# Voltage_Sensing.net
KiCad netlist of a schematic drawn in Altium Designer
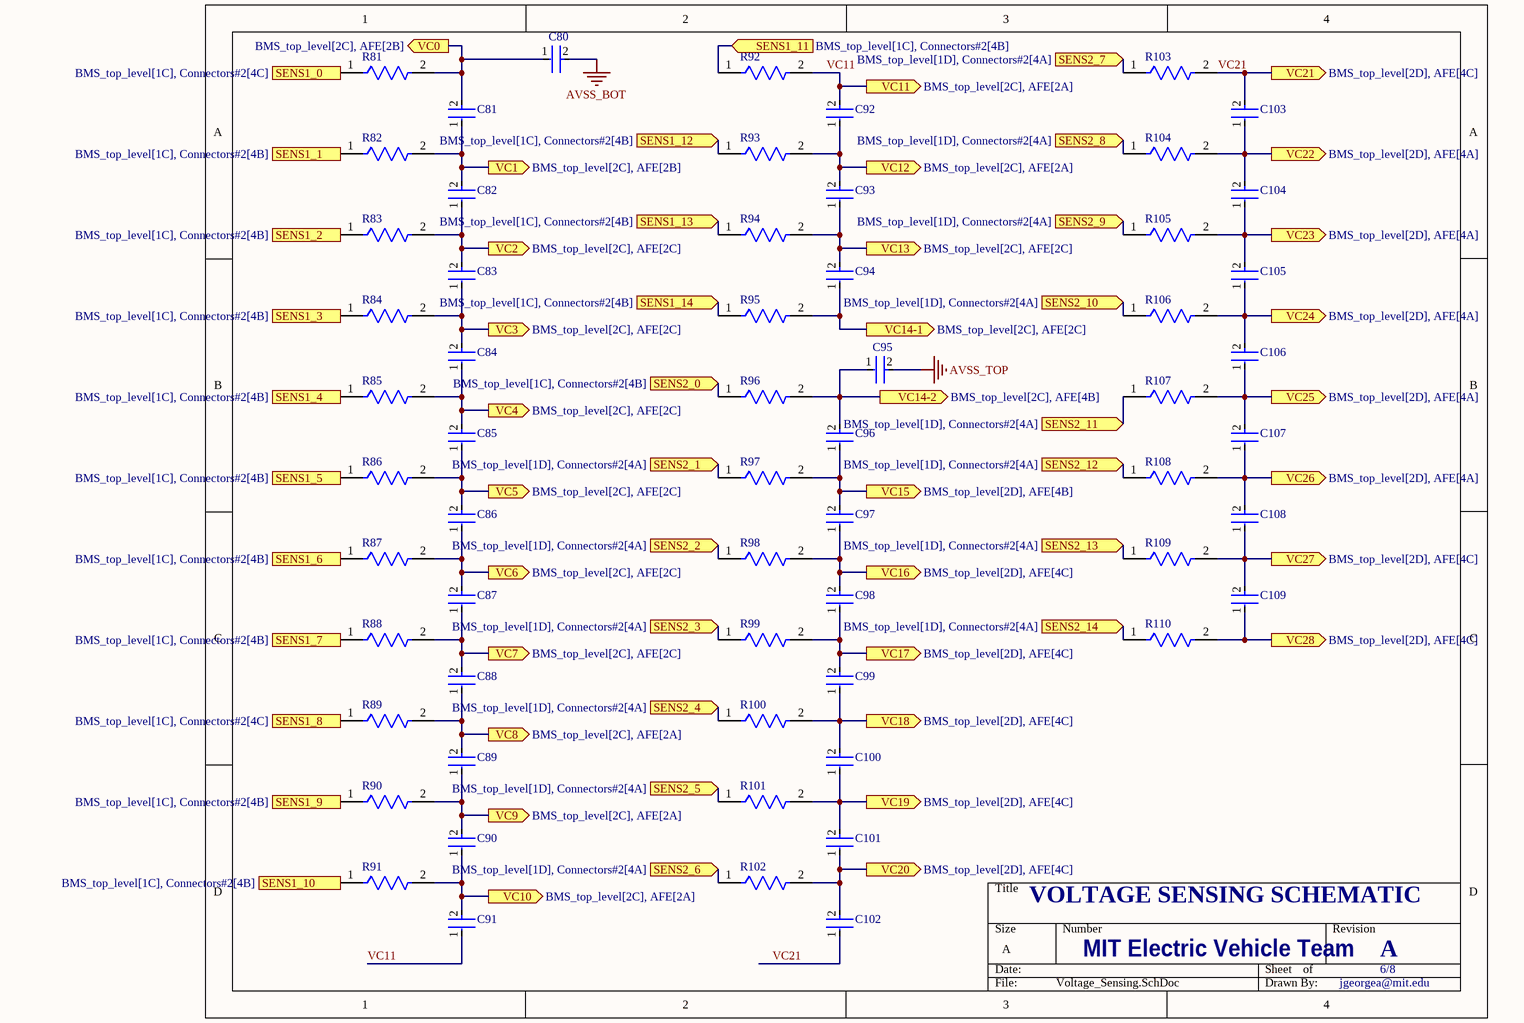
[diagram p0: Voltage_Sensing.SchDoc]

(export (version "E")
  (design (tool "Eeschema 10.0.6"))
  (components
    (comp (ref "C80")
      (value "C1608X7R1C474K080AC")
      (footprint "FP-C1608-080-0_1-IPC_C")
      (description "Multilayer Ceramic Capacitors 470nF ±10% 16V X7R SMD 0603")
      (fields (field (name "VOLTAGE") "16V") (field (name "TOLERANCE") "10%"))
      (libsource (lib "Altium Content Vault") (part "236180d848d6139a670b325ea6854c9"))
    )
    (comp (ref "C81")
      (value "C1608X7R1C474K080AC")
      (footprint "FP-C1608-080-0_1-IPC_C")
      (description "Multilayer Ceramic Capacitors 470nF ±10% 16V X7R SMD 0603")
      (fields (field (name "VOLTAGE") "16V") (field (name "TOLERANCE") "10%"))
      (libsource (lib "Altium Content Vault") (part "236180d848d6139a670b325ea6854c9"))
    )
    (comp (ref "C82")
      (value "C1608X7R1C474K080AC")
      (footprint "FP-C1608-080-0_1-IPC_C")
      (description "Multilayer Ceramic Capacitors 470nF ±10% 16V X7R SMD 0603")
      (fields (field (name "VOLTAGE") "16V") (field (name "TOLERANCE") "10%"))
      (libsource (lib "Altium Content Vault") (part "236180d848d6139a670b325ea6854c9"))
    )
    (comp (ref "C83")
      (value "C1608X7R1C474K080AC")
      (footprint "FP-C1608-080-0_1-IPC_C")
      (description "Multilayer Ceramic Capacitors 470nF ±10% 16V X7R SMD 0603")
      (fields (field (name "VOLTAGE") "16V") (field (name "TOLERANCE") "10%"))
      (libsource (lib "Altium Content Vault") (part "236180d848d6139a670b325ea6854c9"))
    )
    (comp (ref "C84")
      (value "C1608X7R1C474K080AC")
      (footprint "FP-C1608-080-0_1-IPC_C")
      (description "Multilayer Ceramic Capacitors 470nF ±10% 16V X7R SMD 0603")
      (fields (field (name "VOLTAGE") "16V") (field (name "TOLERANCE") "10%"))
      (libsource (lib "Altium Content Vault") (part "236180d848d6139a670b325ea6854c9"))
    )
    (comp (ref "C85")
      (value "C1608X7R1C474K080AC")
      (footprint "FP-C1608-080-0_1-IPC_C")
      (description "Multilayer Ceramic Capacitors 470nF ±10% 16V X7R SMD 0603")
      (fields (field (name "VOLTAGE") "16V") (field (name "TOLERANCE") "10%"))
      (libsource (lib "Altium Content Vault") (part "236180d848d6139a670b325ea6854c9"))
    )
    (comp (ref "C86")
      (value "C1608X7R1C474K080AC")
      (footprint "FP-C1608-080-0_1-IPC_C")
      (description "Multilayer Ceramic Capacitors 470nF ±10% 16V X7R SMD 0603")
      (fields (field (name "VOLTAGE") "16V") (field (name "TOLERANCE") "10%"))
      (libsource (lib "Altium Content Vault") (part "236180d848d6139a670b325ea6854c9"))
    )
    (comp (ref "C87")
      (value "C1608X7R1C474K080AC")
      (footprint "FP-C1608-080-0_1-IPC_C")
      (description "Multilayer Ceramic Capacitors 470nF ±10% 16V X7R SMD 0603")
      (fields (field (name "VOLTAGE") "16V") (field (name "TOLERANCE") "10%"))
      (libsource (lib "Altium Content Vault") (part "236180d848d6139a670b325ea6854c9"))
    )
    (comp (ref "C88")
      (value "C1608X7R1C474K080AC")
      (footprint "FP-C1608-080-0_1-IPC_C")
      (description "Multilayer Ceramic Capacitors 470nF ±10% 16V X7R SMD 0603")
      (fields (field (name "VOLTAGE") "16V") (field (name "TOLERANCE") "10%"))
      (libsource (lib "Altium Content Vault") (part "236180d848d6139a670b325ea6854c9"))
    )
    (comp (ref "C89")
      (value "C1608X7R1C474K080AC")
      (footprint "FP-C1608-080-0_1-IPC_C")
      (description "Multilayer Ceramic Capacitors 470nF ±10% 16V X7R SMD 0603")
      (fields (field (name "VOLTAGE") "16V") (field (name "TOLERANCE") "10%"))
      (libsource (lib "Altium Content Vault") (part "236180d848d6139a670b325ea6854c9"))
    )
    (comp (ref "C90")
      (value "C1608X7R1C474K080AC")
      (footprint "FP-C1608-080-0_1-IPC_C")
      (description "Multilayer Ceramic Capacitors 470nF ±10% 16V X7R SMD 0603")
      (fields (field (name "VOLTAGE") "16V") (field (name "TOLERANCE") "10%"))
      (libsource (lib "Altium Content Vault") (part "236180d848d6139a670b325ea6854c9"))
    )
    (comp (ref "C91")
      (value "C1608X7R1C474K080AC")
      (footprint "FP-C1608-080-0_1-IPC_C")
      (description "Multilayer Ceramic Capacitors 470nF ±10% 16V X7R SMD 0603")
      (fields (field (name "VOLTAGE") "16V") (field (name "TOLERANCE") "10%"))
      (libsource (lib "Altium Content Vault") (part "236180d848d6139a670b325ea6854c9"))
    )
    (comp (ref "C92")
      (value "C1608X7R1C474K080AC")
      (footprint "FP-C1608-080-0_1-IPC_C")
      (description "Multilayer Ceramic Capacitors 470nF ±10% 16V X7R SMD 0603")
      (fields (field (name "VOLTAGE") "16V") (field (name "TOLERANCE") "10%"))
      (libsource (lib "Altium Content Vault") (part "236180d848d6139a670b325ea6854c9"))
    )
    (comp (ref "C93")
      (value "C1608X7R1C474K080AC")
      (footprint "FP-C1608-080-0_1-IPC_C")
      (description "Multilayer Ceramic Capacitors 470nF ±10% 16V X7R SMD 0603")
      (fields (field (name "VOLTAGE") "16V") (field (name "TOLERANCE") "10%"))
      (libsource (lib "Altium Content Vault") (part "236180d848d6139a670b325ea6854c9"))
    )
    (comp (ref "C94")
      (value "C1608X7R1C474K080AC")
      (footprint "FP-C1608-080-0_1-IPC_C")
      (description "Multilayer Ceramic Capacitors 470nF ±10% 16V X7R SMD 0603")
      (fields (field (name "VOLTAGE") "16V") (field (name "TOLERANCE") "10%"))
      (libsource (lib "Altium Content Vault") (part "236180d848d6139a670b325ea6854c9"))
    )
    (comp (ref "C95")
      (value "C1608X7R1C474K080AC")
      (footprint "FP-C1608-080-0_1-IPC_C")
      (description "Multilayer Ceramic Capacitors 470nF ±10% 16V X7R SMD 0603")
      (fields (field (name "VOLTAGE") "16V") (field (name "TOLERANCE") "10%"))
      (libsource (lib "Altium Content Vault") (part "236180d848d6139a670b325ea6854c9"))
    )
    (comp (ref "C96")
      (value "C1608X7R1C474K080AC")
      (footprint "FP-C1608-080-0_1-IPC_C")
      (description "Multilayer Ceramic Capacitors 470nF ±10% 16V X7R SMD 0603")
      (fields (field (name "VOLTAGE") "16V") (field (name "TOLERANCE") "10%"))
      (libsource (lib "Altium Content Vault") (part "236180d848d6139a670b325ea6854c9"))
    )
    (comp (ref "C97")
      (value "C1608X7R1C474K080AC")
      (footprint "FP-C1608-080-0_1-IPC_C")
      (description "Multilayer Ceramic Capacitors 470nF ±10% 16V X7R SMD 0603")
      (fields (field (name "VOLTAGE") "16V") (field (name "TOLERANCE") "10%"))
      (libsource (lib "Altium Content Vault") (part "236180d848d6139a670b325ea6854c9"))
    )
    (comp (ref "C98")
      (value "C1608X7R1C474K080AC")
      (footprint "FP-C1608-080-0_1-IPC_C")
      (description "Multilayer Ceramic Capacitors 470nF ±10% 16V X7R SMD 0603")
      (fields (field (name "VOLTAGE") "16V") (field (name "TOLERANCE") "10%"))
      (libsource (lib "Altium Content Vault") (part "236180d848d6139a670b325ea6854c9"))
    )
    (comp (ref "C99")
      (value "C1608X7R1C474K080AC")
      (footprint "FP-C1608-080-0_1-IPC_C")
      (description "Multilayer Ceramic Capacitors 470nF ±10% 16V X7R SMD 0603")
      (fields (field (name "VOLTAGE") "16V") (field (name "TOLERANCE") "10%"))
      (libsource (lib "Altium Content Vault") (part "236180d848d6139a670b325ea6854c9"))
    )
    (comp (ref "C100")
      (value "C1608X7R1C474K080AC")
      (footprint "FP-C1608-080-0_1-IPC_C")
      (description "Multilayer Ceramic Capacitors 470nF ±10% 16V X7R SMD 0603")
      (fields (field (name "VOLTAGE") "16V") (field (name "TOLERANCE") "10%"))
      (libsource (lib "Altium Content Vault") (part "236180d848d6139a670b325ea6854c9"))
    )
    (comp (ref "C101")
      (value "C1608X7R1C474K080AC")
      (footprint "FP-C1608-080-0_1-IPC_C")
      (description "Multilayer Ceramic Capacitors 470nF ±10% 16V X7R SMD 0603")
      (fields (field (name "VOLTAGE") "16V") (field (name "TOLERANCE") "10%"))
      (libsource (lib "Altium Content Vault") (part "236180d848d6139a670b325ea6854c9"))
    )
    (comp (ref "C102")
      (value "C1608X7R1C474K080AC")
      (footprint "FP-C1608-080-0_1-IPC_C")
      (description "Multilayer Ceramic Capacitors 470nF ±10% 16V X7R SMD 0603")
      (fields (field (name "VOLTAGE") "16V") (field (name "TOLERANCE") "10%"))
      (libsource (lib "Altium Content Vault") (part "236180d848d6139a670b325ea6854c9"))
    )
    (comp (ref "C103")
      (value "C1608X7R1C474K080AC")
      (footprint "FP-C1608-080-0_1-IPC_C")
      (description "Multilayer Ceramic Capacitors 470nF ±10% 16V X7R SMD 0603")
      (fields (field (name "VOLTAGE") "16V") (field (name "TOLERANCE") "10%"))
      (libsource (lib "Altium Content Vault") (part "236180d848d6139a670b325ea6854c9"))
    )
    (comp (ref "C104")
      (value "C1608X7R1C474K080AC")
      (footprint "FP-C1608-080-0_1-IPC_C")
      (description "Multilayer Ceramic Capacitors 470nF ±10% 16V X7R SMD 0603")
      (fields (field (name "VOLTAGE") "16V") (field (name "TOLERANCE") "10%"))
      (libsource (lib "Altium Content Vault") (part "236180d848d6139a670b325ea6854c9"))
    )
    (comp (ref "C105")
      (value "C1608X7R1C474K080AC")
      (footprint "FP-C1608-080-0_1-IPC_C")
      (description "Multilayer Ceramic Capacitors 470nF ±10% 16V X7R SMD 0603")
      (fields (field (name "VOLTAGE") "16V") (field (name "TOLERANCE") "10%"))
      (libsource (lib "Altium Content Vault") (part "236180d848d6139a670b325ea6854c9"))
    )
    (comp (ref "C106")
      (value "C1608X7R1C474K080AC")
      (footprint "FP-C1608-080-0_1-IPC_C")
      (description "Multilayer Ceramic Capacitors 470nF ±10% 16V X7R SMD 0603")
      (fields (field (name "VOLTAGE") "16V") (field (name "TOLERANCE") "10%"))
      (libsource (lib "Altium Content Vault") (part "236180d848d6139a670b325ea6854c9"))
    )
    (comp (ref "C107")
      (value "C1608X7R1C474K080AC")
      (footprint "FP-C1608-080-0_1-IPC_C")
      (description "Multilayer Ceramic Capacitors 470nF ±10% 16V X7R SMD 0603")
      (fields (field (name "VOLTAGE") "16V") (field (name "TOLERANCE") "10%"))
      (libsource (lib "Altium Content Vault") (part "236180d848d6139a670b325ea6854c9"))
    )
    (comp (ref "C108")
      (value "C1608X7R1C474K080AC")
      (footprint "FP-C1608-080-0_1-IPC_C")
      (description "Multilayer Ceramic Capacitors 470nF ±10% 16V X7R SMD 0603")
      (fields (field (name "VOLTAGE") "16V") (field (name "TOLERANCE") "10%"))
      (libsource (lib "Altium Content Vault") (part "236180d848d6139a670b325ea6854c9"))
    )
    (comp (ref "C109")
      (value "C1608X7R1C474K080AC")
      (footprint "FP-C1608-080-0_1-IPC_C")
      (description "Multilayer Ceramic Capacitors 470nF ±10% 16V X7R SMD 0603")
      (fields (field (name "VOLTAGE") "16V") (field (name "TOLERANCE") "10%"))
      (libsource (lib "Altium Content Vault") (part "236180d848d6139a670b325ea6854c9"))
    )
    (comp (ref "R81")
      (value "CRCW0805100RJNEAHP")
      (footprint "FP-CRCW0805-HPe3-IPC_C")
      (description "RES Thick Film, 100Ω, 5%, 0.5W, 200ppm/°C, 0805")
      (fields (field (name "TOLERANCE") "5%"))
      (libsource (lib "Altium Content Vault") (part "1029c3af85768c4190bb7ad29bc67b5"))
    )
    (comp (ref "R82")
      (value "CRCW0805100RJNEAHP")
      (footprint "FP-CRCW0805-HPe3-IPC_C")
      (description "RES Thick Film, 100Ω, 5%, 0.5W, 200ppm/°C, 0805")
      (fields (field (name "TOLERANCE") "5%"))
      (libsource (lib "Altium Content Vault") (part "1029c3af85768c4190bb7ad29bc67b5"))
    )
    (comp (ref "R83")
      (value "CRCW0805100RJNEAHP")
      (footprint "FP-CRCW0805-HPe3-IPC_C")
      (description "RES Thick Film, 100Ω, 5%, 0.5W, 200ppm/°C, 0805")
      (fields (field (name "TOLERANCE") "5%"))
      (libsource (lib "Altium Content Vault") (part "1029c3af85768c4190bb7ad29bc67b5"))
    )
    (comp (ref "R84")
      (value "CRCW0805100RJNEAHP")
      (footprint "FP-CRCW0805-HPe3-IPC_C")
      (description "RES Thick Film, 100Ω, 5%, 0.5W, 200ppm/°C, 0805")
      (fields (field (name "TOLERANCE") "5%"))
      (libsource (lib "Altium Content Vault") (part "1029c3af85768c4190bb7ad29bc67b5"))
    )
    (comp (ref "R85")
      (value "CRCW0805100RJNEAHP")
      (footprint "FP-CRCW0805-HPe3-IPC_C")
      (description "RES Thick Film, 100Ω, 5%, 0.5W, 200ppm/°C, 0805")
      (fields (field (name "TOLERANCE") "5%"))
      (libsource (lib "Altium Content Vault") (part "1029c3af85768c4190bb7ad29bc67b5"))
    )
    (comp (ref "R86")
      (value "CRCW0805100RJNEAHP")
      (footprint "FP-CRCW0805-HPe3-IPC_C")
      (description "RES Thick Film, 100Ω, 5%, 0.5W, 200ppm/°C, 0805")
      (fields (field (name "TOLERANCE") "5%"))
      (libsource (lib "Altium Content Vault") (part "1029c3af85768c4190bb7ad29bc67b5"))
    )
    (comp (ref "R87")
      (value "CRCW0805100RJNEAHP")
      (footprint "FP-CRCW0805-HPe3-IPC_C")
      (description "RES Thick Film, 100Ω, 5%, 0.5W, 200ppm/°C, 0805")
      (fields (field (name "TOLERANCE") "5%"))
      (libsource (lib "Altium Content Vault") (part "1029c3af85768c4190bb7ad29bc67b5"))
    )
    (comp (ref "R88")
      (value "CRCW0805100RJNEAHP")
      (footprint "FP-CRCW0805-HPe3-IPC_C")
      (description "RES Thick Film, 100Ω, 5%, 0.5W, 200ppm/°C, 0805")
      (fields (field (name "TOLERANCE") "5%"))
      (libsource (lib "Altium Content Vault") (part "1029c3af85768c4190bb7ad29bc67b5"))
    )
    (comp (ref "R89")
      (value "CRCW0805100RJNEAHP")
      (footprint "FP-CRCW0805-HPe3-IPC_C")
      (description "RES Thick Film, 100Ω, 5%, 0.5W, 200ppm/°C, 0805")
      (fields (field (name "TOLERANCE") "5%"))
      (libsource (lib "Altium Content Vault") (part "1029c3af85768c4190bb7ad29bc67b5"))
    )
    (comp (ref "R90")
      (value "CRCW0805100RJNEAHP")
      (footprint "FP-CRCW0805-HPe3-IPC_C")
      (description "RES Thick Film, 100Ω, 5%, 0.5W, 200ppm/°C, 0805")
      (fields (field (name "TOLERANCE") "5%"))
      (libsource (lib "Altium Content Vault") (part "1029c3af85768c4190bb7ad29bc67b5"))
    )
    (comp (ref "R91")
      (value "CRCW0805100RJNEAHP")
      (footprint "FP-CRCW0805-HPe3-IPC_C")
      (description "RES Thick Film, 100Ω, 5%, 0.5W, 200ppm/°C, 0805")
      (fields (field (name "TOLERANCE") "5%"))
      (libsource (lib "Altium Content Vault") (part "1029c3af85768c4190bb7ad29bc67b5"))
    )
    (comp (ref "R92")
      (value "CRCW0805100RJNEAHP")
      (footprint "FP-CRCW0805-HPe3-IPC_C")
      (description "RES Thick Film, 100Ω, 5%, 0.5W, 200ppm/°C, 0805")
      (fields (field (name "TOLERANCE") "5%"))
      (libsource (lib "Altium Content Vault") (part "1029c3af85768c4190bb7ad29bc67b5"))
    )
    (comp (ref "R93")
      (value "CRCW0805100RJNEAHP")
      (footprint "FP-CRCW0805-HPe3-IPC_C")
      (description "RES Thick Film, 100Ω, 5%, 0.5W, 200ppm/°C, 0805")
      (fields (field (name "TOLERANCE") "5%"))
      (libsource (lib "Altium Content Vault") (part "1029c3af85768c4190bb7ad29bc67b5"))
    )
    (comp (ref "R94")
      (value "CRCW0805100RJNEAHP")
      (footprint "FP-CRCW0805-HPe3-IPC_C")
      (description "RES Thick Film, 100Ω, 5%, 0.5W, 200ppm/°C, 0805")
      (fields (field (name "TOLERANCE") "5%"))
      (libsource (lib "Altium Content Vault") (part "1029c3af85768c4190bb7ad29bc67b5"))
    )
    (comp (ref "R95")
      (value "CRCW0805100RJNEAHP")
      (footprint "FP-CRCW0805-HPe3-IPC_C")
      (description "RES Thick Film, 100Ω, 5%, 0.5W, 200ppm/°C, 0805")
      (fields (field (name "TOLERANCE") "5%"))
      (libsource (lib "Altium Content Vault") (part "1029c3af85768c4190bb7ad29bc67b5"))
    )
    (comp (ref "R96")
      (value "CRCW0805100RJNEAHP")
      (footprint "FP-CRCW0805-HPe3-IPC_C")
      (description "RES Thick Film, 100Ω, 5%, 0.5W, 200ppm/°C, 0805")
      (fields (field (name "TOLERANCE") "5%"))
      (libsource (lib "Altium Content Vault") (part "1029c3af85768c4190bb7ad29bc67b5"))
    )
    (comp (ref "R97")
      (value "CRCW0805100RJNEAHP")
      (footprint "FP-CRCW0805-HPe3-IPC_C")
      (description "RES Thick Film, 100Ω, 5%, 0.5W, 200ppm/°C, 0805")
      (fields (field (name "TOLERANCE") "5%"))
      (libsource (lib "Altium Content Vault") (part "1029c3af85768c4190bb7ad29bc67b5"))
    )
    (comp (ref "R98")
      (value "CRCW0805100RJNEAHP")
      (footprint "FP-CRCW0805-HPe3-IPC_C")
      (description "RES Thick Film, 100Ω, 5%, 0.5W, 200ppm/°C, 0805")
      (fields (field (name "TOLERANCE") "5%"))
      (libsource (lib "Altium Content Vault") (part "1029c3af85768c4190bb7ad29bc67b5"))
    )
    (comp (ref "R99")
      (value "CRCW0805100RJNEAHP")
      (footprint "FP-CRCW0805-HPe3-IPC_C")
      (description "RES Thick Film, 100Ω, 5%, 0.5W, 200ppm/°C, 0805")
      (fields (field (name "TOLERANCE") "5%"))
      (libsource (lib "Altium Content Vault") (part "1029c3af85768c4190bb7ad29bc67b5"))
    )
    (comp (ref "R100")
      (value "CRCW0805100RJNEAHP")
      (footprint "FP-CRCW0805-HPe3-IPC_C")
      (description "RES Thick Film, 100Ω, 5%, 0.5W, 200ppm/°C, 0805")
      (fields (field (name "TOLERANCE") "5%"))
      (libsource (lib "Altium Content Vault") (part "1029c3af85768c4190bb7ad29bc67b5"))
    )
    (comp (ref "R101")
      (value "CRCW0805100RJNEAHP")
      (footprint "FP-CRCW0805-HPe3-IPC_C")
      (description "RES Thick Film, 100Ω, 5%, 0.5W, 200ppm/°C, 0805")
      (fields (field (name "TOLERANCE") "5%"))
      (libsource (lib "Altium Content Vault") (part "1029c3af85768c4190bb7ad29bc67b5"))
    )
    (comp (ref "R102")
      (value "CRCW0805100RJNEAHP")
      (footprint "FP-CRCW0805-HPe3-IPC_C")
      (description "RES Thick Film, 100Ω, 5%, 0.5W, 200ppm/°C, 0805")
      (fields (field (name "TOLERANCE") "5%"))
      (libsource (lib "Altium Content Vault") (part "1029c3af85768c4190bb7ad29bc67b5"))
    )
    (comp (ref "R103")
      (value "CRCW0805100RJNEAHP")
      (footprint "FP-CRCW0805-HPe3-IPC_C")
      (description "RES Thick Film, 100Ω, 5%, 0.5W, 200ppm/°C, 0805")
      (fields (field (name "TOLERANCE") "5%"))
      (libsource (lib "Altium Content Vault") (part "1029c3af85768c4190bb7ad29bc67b5"))
    )
    (comp (ref "R104")
      (value "CRCW0805100RJNEAHP")
      (footprint "FP-CRCW0805-HPe3-IPC_C")
      (description "RES Thick Film, 100Ω, 5%, 0.5W, 200ppm/°C, 0805")
      (fields (field (name "TOLERANCE") "5%"))
      (libsource (lib "Altium Content Vault") (part "1029c3af85768c4190bb7ad29bc67b5"))
    )
    (comp (ref "R105")
      (value "CRCW0805100RJNEAHP")
      (footprint "FP-CRCW0805-HPe3-IPC_C")
      (description "RES Thick Film, 100Ω, 5%, 0.5W, 200ppm/°C, 0805")
      (fields (field (name "TOLERANCE") "5%"))
      (libsource (lib "Altium Content Vault") (part "1029c3af85768c4190bb7ad29bc67b5"))
    )
    (comp (ref "R106")
      (value "CRCW0805100RJNEAHP")
      (footprint "FP-CRCW0805-HPe3-IPC_C")
      (description "RES Thick Film, 100Ω, 5%, 0.5W, 200ppm/°C, 0805")
      (fields (field (name "TOLERANCE") "5%"))
      (libsource (lib "Altium Content Vault") (part "1029c3af85768c4190bb7ad29bc67b5"))
    )
    (comp (ref "R107")
      (value "CRCW0805100RJNEAHP")
      (footprint "FP-CRCW0805-HPe3-IPC_C")
      (description "RES Thick Film, 100Ω, 5%, 0.5W, 200ppm/°C, 0805")
      (fields (field (name "TOLERANCE") "5%"))
      (libsource (lib "Altium Content Vault") (part "1029c3af85768c4190bb7ad29bc67b5"))
    )
    (comp (ref "R108")
      (value "CRCW0805100RJNEAHP")
      (footprint "FP-CRCW0805-HPe3-IPC_C")
      (description "RES Thick Film, 100Ω, 5%, 0.5W, 200ppm/°C, 0805")
      (fields (field (name "TOLERANCE") "5%"))
      (libsource (lib "Altium Content Vault") (part "1029c3af85768c4190bb7ad29bc67b5"))
    )
    (comp (ref "R109")
      (value "CRCW0805100RJNEAHP")
      (footprint "FP-CRCW0805-HPe3-IPC_C")
      (description "RES Thick Film, 100Ω, 5%, 0.5W, 200ppm/°C, 0805")
      (fields (field (name "TOLERANCE") "5%"))
      (libsource (lib "Altium Content Vault") (part "1029c3af85768c4190bb7ad29bc67b5"))
    )
    (comp (ref "R110")
      (value "CRCW0805100RJNEAHP")
      (footprint "FP-CRCW0805-HPe3-IPC_C")
      (description "RES Thick Film, 100Ω, 5%, 0.5W, 200ppm/°C, 0805")
      (fields (field (name "TOLERANCE") "5%"))
      (libsource (lib "Altium Content Vault") (part "1029c3af85768c4190bb7ad29bc67b5"))
    )
  )
  (nets
    (net (code "1") (name "/SENS1_0") (class "Default")
      (node (ref "R81") (pin "1") (pinfunction "1_1") (pintype "passive"))
    )
    (net (code "2") (name "/SENS1_1") (class "Default")
      (node (ref "R82") (pin "1") (pinfunction "1_1") (pintype "passive"))
    )
    (net (code "3") (name "/SENS1_2") (class "Default")
      (node (ref "R83") (pin "1") (pinfunction "1_1") (pintype "passive"))
    )
    (net (code "4") (name "/SENS1_3") (class "Default")
      (node (ref "R84") (pin "1") (pinfunction "1_1") (pintype "passive"))
    )
    (net (code "5") (name "/SENS1_4") (class "Default")
      (node (ref "R85") (pin "1") (pinfunction "1_1") (pintype "passive"))
    )
    (net (code "6") (name "/SENS1_5") (class "Default")
      (node (ref "R86") (pin "1") (pinfunction "1_1") (pintype "passive"))
    )
    (net (code "7") (name "/SENS1_6") (class "Default")
      (node (ref "R87") (pin "1") (pinfunction "1_1") (pintype "passive"))
    )
    (net (code "8") (name "/SENS1_7") (class "Default")
      (node (ref "R88") (pin "1") (pinfunction "1_1") (pintype "passive"))
    )
    (net (code "9") (name "/SENS1_8") (class "Default")
      (node (ref "R89") (pin "1") (pinfunction "1_1") (pintype "passive"))
    )
    (net (code "10") (name "/SENS1_9") (class "Default")
      (node (ref "R90") (pin "1") (pinfunction "1_1") (pintype "passive"))
    )
    (net (code "11") (name "/SENS1_10") (class "Default")
      (node (ref "R91") (pin "1") (pinfunction "1_1") (pintype "passive"))
    )
    (net (code "12") (name "/SENS1_11") (class "Default")
      (node (ref "R92") (pin "1") (pinfunction "1_1") (pintype "passive"))
    )
    (net (code "13") (name "/SENS1_12") (class "Default")
      (node (ref "R93") (pin "1") (pinfunction "1_1") (pintype "passive"))
    )
    (net (code "14") (name "/SENS1_13") (class "Default")
      (node (ref "R94") (pin "1") (pinfunction "1_1") (pintype "passive"))
    )
    (net (code "15") (name "/SENS1_14") (class "Default")
      (node (ref "R95") (pin "1") (pinfunction "1_1") (pintype "passive"))
    )
    (net (code "16") (name "/SENS2_0") (class "Default")
      (node (ref "R96") (pin "1") (pinfunction "1_1") (pintype "passive"))
    )
    (net (code "17") (name "/SENS2_1") (class "Default")
      (node (ref "R97") (pin "1") (pinfunction "1_1") (pintype "passive"))
    )
    (net (code "18") (name "/SENS2_2") (class "Default")
      (node (ref "R98") (pin "1") (pinfunction "1_1") (pintype "passive"))
    )
    (net (code "19") (name "/SENS2_3") (class "Default")
      (node (ref "R99") (pin "1") (pinfunction "1_1") (pintype "passive"))
    )
    (net (code "20") (name "/SENS2_4") (class "Default")
      (node (ref "R100") (pin "1") (pinfunction "1_1") (pintype "passive"))
    )
    (net (code "21") (name "/SENS2_5") (class "Default")
      (node (ref "R101") (pin "1") (pinfunction "1_1") (pintype "passive"))
    )
    (net (code "22") (name "/SENS2_6") (class "Default")
      (node (ref "R102") (pin "1") (pinfunction "1_1") (pintype "passive"))
    )
    (net (code "23") (name "/SENS2_7") (class "Default")
      (node (ref "R103") (pin "1") (pinfunction "1_1") (pintype "passive"))
    )
    (net (code "24") (name "/SENS2_8") (class "Default")
      (node (ref "R104") (pin "1") (pinfunction "1_1") (pintype "passive"))
    )
    (net (code "25") (name "/SENS2_9") (class "Default")
      (node (ref "R105") (pin "1") (pinfunction "1_1") (pintype "passive"))
    )
    (net (code "26") (name "/SENS2_10") (class "Default")
      (node (ref "R106") (pin "1") (pinfunction "1_1") (pintype "passive"))
    )
    (net (code "27") (name "/SENS2_11") (class "Default")
      (node (ref "R107") (pin "1") (pinfunction "1_1") (pintype "passive"))
    )
    (net (code "28") (name "/SENS2_12") (class "Default")
      (node (ref "R108") (pin "1") (pinfunction "1_1") (pintype "passive"))
    )
    (net (code "29") (name "/SENS2_13") (class "Default")
      (node (ref "R109") (pin "1") (pinfunction "1_1") (pintype "passive"))
    )
    (net (code "30") (name "/SENS2_14") (class "Default")
      (node (ref "R110") (pin "1") (pinfunction "1_1") (pintype "passive"))
    )
    (net (code "31") (name "/VC0") (class "Default")
      (node (ref "C80") (pin "1") (pinfunction "1_1") (pintype "passive"))
      (node (ref "C81") (pin "2") (pinfunction "2_2") (pintype "passive"))
      (node (ref "R81") (pin "2") (pinfunction "2_2") (pintype "passive"))
    )
    (net (code "32") (name "/VC1") (class "Default")
      (node (ref "C81") (pin "1") (pinfunction "1_1") (pintype "passive"))
      (node (ref "C82") (pin "2") (pinfunction "2_2") (pintype "passive"))
      (node (ref "R82") (pin "2") (pinfunction "2_2") (pintype "passive"))
    )
    (net (code "33") (name "/VC2") (class "Default")
      (node (ref "C82") (pin "1") (pinfunction "1_1") (pintype "passive"))
      (node (ref "C83") (pin "2") (pinfunction "2_2") (pintype "passive"))
      (node (ref "R83") (pin "2") (pinfunction "2_2") (pintype "passive"))
    )
    (net (code "34") (name "/VC3") (class "Default")
      (node (ref "C83") (pin "1") (pinfunction "1_1") (pintype "passive"))
      (node (ref "C84") (pin "2") (pinfunction "2_2") (pintype "passive"))
      (node (ref "R84") (pin "2") (pinfunction "2_2") (pintype "passive"))
    )
    (net (code "35") (name "/VC4") (class "Default")
      (node (ref "C84") (pin "1") (pinfunction "1_1") (pintype "passive"))
      (node (ref "C85") (pin "2") (pinfunction "2_2") (pintype "passive"))
      (node (ref "R85") (pin "2") (pinfunction "2_2") (pintype "passive"))
    )
    (net (code "36") (name "/VC5") (class "Default")
      (node (ref "C85") (pin "1") (pinfunction "1_1") (pintype "passive"))
      (node (ref "C86") (pin "2") (pinfunction "2_2") (pintype "passive"))
      (node (ref "R86") (pin "2") (pinfunction "2_2") (pintype "passive"))
    )
    (net (code "37") (name "/VC6") (class "Default")
      (node (ref "C86") (pin "1") (pinfunction "1_1") (pintype "passive"))
      (node (ref "C87") (pin "2") (pinfunction "2_2") (pintype "passive"))
      (node (ref "R87") (pin "2") (pinfunction "2_2") (pintype "passive"))
    )
    (net (code "38") (name "/VC7") (class "Default")
      (node (ref "C87") (pin "1") (pinfunction "1_1") (pintype "passive"))
      (node (ref "C88") (pin "2") (pinfunction "2_2") (pintype "passive"))
      (node (ref "R88") (pin "2") (pinfunction "2_2") (pintype "passive"))
    )
    (net (code "39") (name "/VC8") (class "Default")
      (node (ref "C88") (pin "1") (pinfunction "1_1") (pintype "passive"))
      (node (ref "C89") (pin "2") (pinfunction "2_2") (pintype "passive"))
      (node (ref "R89") (pin "2") (pinfunction "2_2") (pintype "passive"))
    )
    (net (code "40") (name "/VC9") (class "Default")
      (node (ref "C89") (pin "1") (pinfunction "1_1") (pintype "passive"))
      (node (ref "C90") (pin "2") (pinfunction "2_2") (pintype "passive"))
      (node (ref "R90") (pin "2") (pinfunction "2_2") (pintype "passive"))
    )
    (net (code "41") (name "/VC10") (class "Default")
      (node (ref "C90") (pin "1") (pinfunction "1_1") (pintype "passive"))
      (node (ref "C91") (pin "2") (pinfunction "2_2") (pintype "passive"))
      (node (ref "R91") (pin "2") (pinfunction "2_2") (pintype "passive"))
    )
    (net (code "42") (name "/VC11") (class "Default")
      (node (ref "C91") (pin "1") (pinfunction "1_1") (pintype "passive"))
      (node (ref "C92") (pin "2") (pinfunction "2_2") (pintype "passive"))
      (node (ref "R92") (pin "2") (pinfunction "2_2") (pintype "passive"))
    )
    (net (code "43") (name "/VC12") (class "Default")
      (node (ref "C92") (pin "1") (pinfunction "1_1") (pintype "passive"))
      (node (ref "C93") (pin "2") (pinfunction "2_2") (pintype "passive"))
      (node (ref "R93") (pin "2") (pinfunction "2_2") (pintype "passive"))
    )
    (net (code "44") (name "/VC13") (class "Default")
      (node (ref "C93") (pin "1") (pinfunction "1_1") (pintype "passive"))
      (node (ref "C94") (pin "2") (pinfunction "2_2") (pintype "passive"))
      (node (ref "R94") (pin "2") (pinfunction "2_2") (pintype "passive"))
    )
    (net (code "45") (name "/VC14-1") (class "Default")
      (node (ref "C94") (pin "1") (pinfunction "1_1") (pintype "passive"))
      (node (ref "R95") (pin "2") (pinfunction "2_2") (pintype "passive"))
    )
    (net (code "46") (name "/VC14-2") (class "Default")
      (node (ref "C95") (pin "1") (pinfunction "1_1") (pintype "passive"))
      (node (ref "C96") (pin "2") (pinfunction "2_2") (pintype "passive"))
      (node (ref "R96") (pin "2") (pinfunction "2_2") (pintype "passive"))
    )
    (net (code "47") (name "/VC15") (class "Default")
      (node (ref "C96") (pin "1") (pinfunction "1_1") (pintype "passive"))
      (node (ref "C97") (pin "2") (pinfunction "2_2") (pintype "passive"))
      (node (ref "R97") (pin "2") (pinfunction "2_2") (pintype "passive"))
    )
    (net (code "48") (name "/VC16") (class "Default")
      (node (ref "C97") (pin "1") (pinfunction "1_1") (pintype "passive"))
      (node (ref "C98") (pin "2") (pinfunction "2_2") (pintype "passive"))
      (node (ref "R98") (pin "2") (pinfunction "2_2") (pintype "passive"))
    )
    (net (code "49") (name "/VC17") (class "Default")
      (node (ref "C98") (pin "1") (pinfunction "1_1") (pintype "passive"))
      (node (ref "C99") (pin "2") (pinfunction "2_2") (pintype "passive"))
      (node (ref "R99") (pin "2") (pinfunction "2_2") (pintype "passive"))
    )
    (net (code "50") (name "/VC18") (class "Default")
      (node (ref "C100") (pin "2") (pinfunction "2_2") (pintype "passive"))
      (node (ref "C99") (pin "1") (pinfunction "1_1") (pintype "passive"))
      (node (ref "R100") (pin "2") (pinfunction "2_2") (pintype "passive"))
    )
    (net (code "51") (name "/VC19") (class "Default")
      (node (ref "C100") (pin "1") (pinfunction "1_1") (pintype "passive"))
      (node (ref "C101") (pin "2") (pinfunction "2_2") (pintype "passive"))
      (node (ref "R101") (pin "2") (pinfunction "2_2") (pintype "passive"))
    )
    (net (code "52") (name "/VC20") (class "Default")
      (node (ref "C101") (pin "1") (pinfunction "1_1") (pintype "passive"))
      (node (ref "C102") (pin "2") (pinfunction "2_2") (pintype "passive"))
      (node (ref "R102") (pin "2") (pinfunction "2_2") (pintype "passive"))
    )
    (net (code "53") (name "/VC21") (class "Default")
      (node (ref "C102") (pin "1") (pinfunction "1_1") (pintype "passive"))
      (node (ref "C103") (pin "2") (pinfunction "2_2") (pintype "passive"))
      (node (ref "R103") (pin "2") (pinfunction "2_2") (pintype "passive"))
    )
    (net (code "54") (name "/VC22") (class "Default")
      (node (ref "C103") (pin "1") (pinfunction "1_1") (pintype "passive"))
      (node (ref "C104") (pin "2") (pinfunction "2_2") (pintype "passive"))
      (node (ref "R104") (pin "2") (pinfunction "2_2") (pintype "passive"))
    )
    (net (code "55") (name "/VC23") (class "Default")
      (node (ref "C104") (pin "1") (pinfunction "1_1") (pintype "passive"))
      (node (ref "C105") (pin "2") (pinfunction "2_2") (pintype "passive"))
      (node (ref "R105") (pin "2") (pinfunction "2_2") (pintype "passive"))
    )
    (net (code "56") (name "/VC24") (class "Default")
      (node (ref "C105") (pin "1") (pinfunction "1_1") (pintype "passive"))
      (node (ref "C106") (pin "2") (pinfunction "2_2") (pintype "passive"))
      (node (ref "R106") (pin "2") (pinfunction "2_2") (pintype "passive"))
    )
    (net (code "57") (name "/VC25") (class "Default")
      (node (ref "C106") (pin "1") (pinfunction "1_1") (pintype "passive"))
      (node (ref "C107") (pin "2") (pinfunction "2_2") (pintype "passive"))
      (node (ref "R107") (pin "2") (pinfunction "2_2") (pintype "passive"))
    )
    (net (code "58") (name "/VC26") (class "Default")
      (node (ref "C107") (pin "1") (pinfunction "1_1") (pintype "passive"))
      (node (ref "C108") (pin "2") (pinfunction "2_2") (pintype "passive"))
      (node (ref "R108") (pin "2") (pinfunction "2_2") (pintype "passive"))
    )
    (net (code "59") (name "/VC27") (class "Default")
      (node (ref "C108") (pin "1") (pinfunction "1_1") (pintype "passive"))
      (node (ref "C109") (pin "2") (pinfunction "2_2") (pintype "passive"))
      (node (ref "R109") (pin "2") (pinfunction "2_2") (pintype "passive"))
    )
    (net (code "60") (name "/VC28") (class "Default")
      (node (ref "C109") (pin "1") (pinfunction "1_1") (pintype "passive"))
      (node (ref "R110") (pin "2") (pinfunction "2_2") (pintype "passive"))
    )
    (net (code "61") (name "AVSS_BOT") (class "Default")
      (node (ref "C80") (pin "2") (pinfunction "2_2") (pintype "passive"))
    )
    (net (code "62") (name "AVSS_TOP") (class "Default")
      (node (ref "C95") (pin "2") (pinfunction "2_2") (pintype "passive"))
    )
  )
)
